# SCH_nfc-card_2024-10-30.net
KiCad netlist of a schematic drawn in EasyEDA
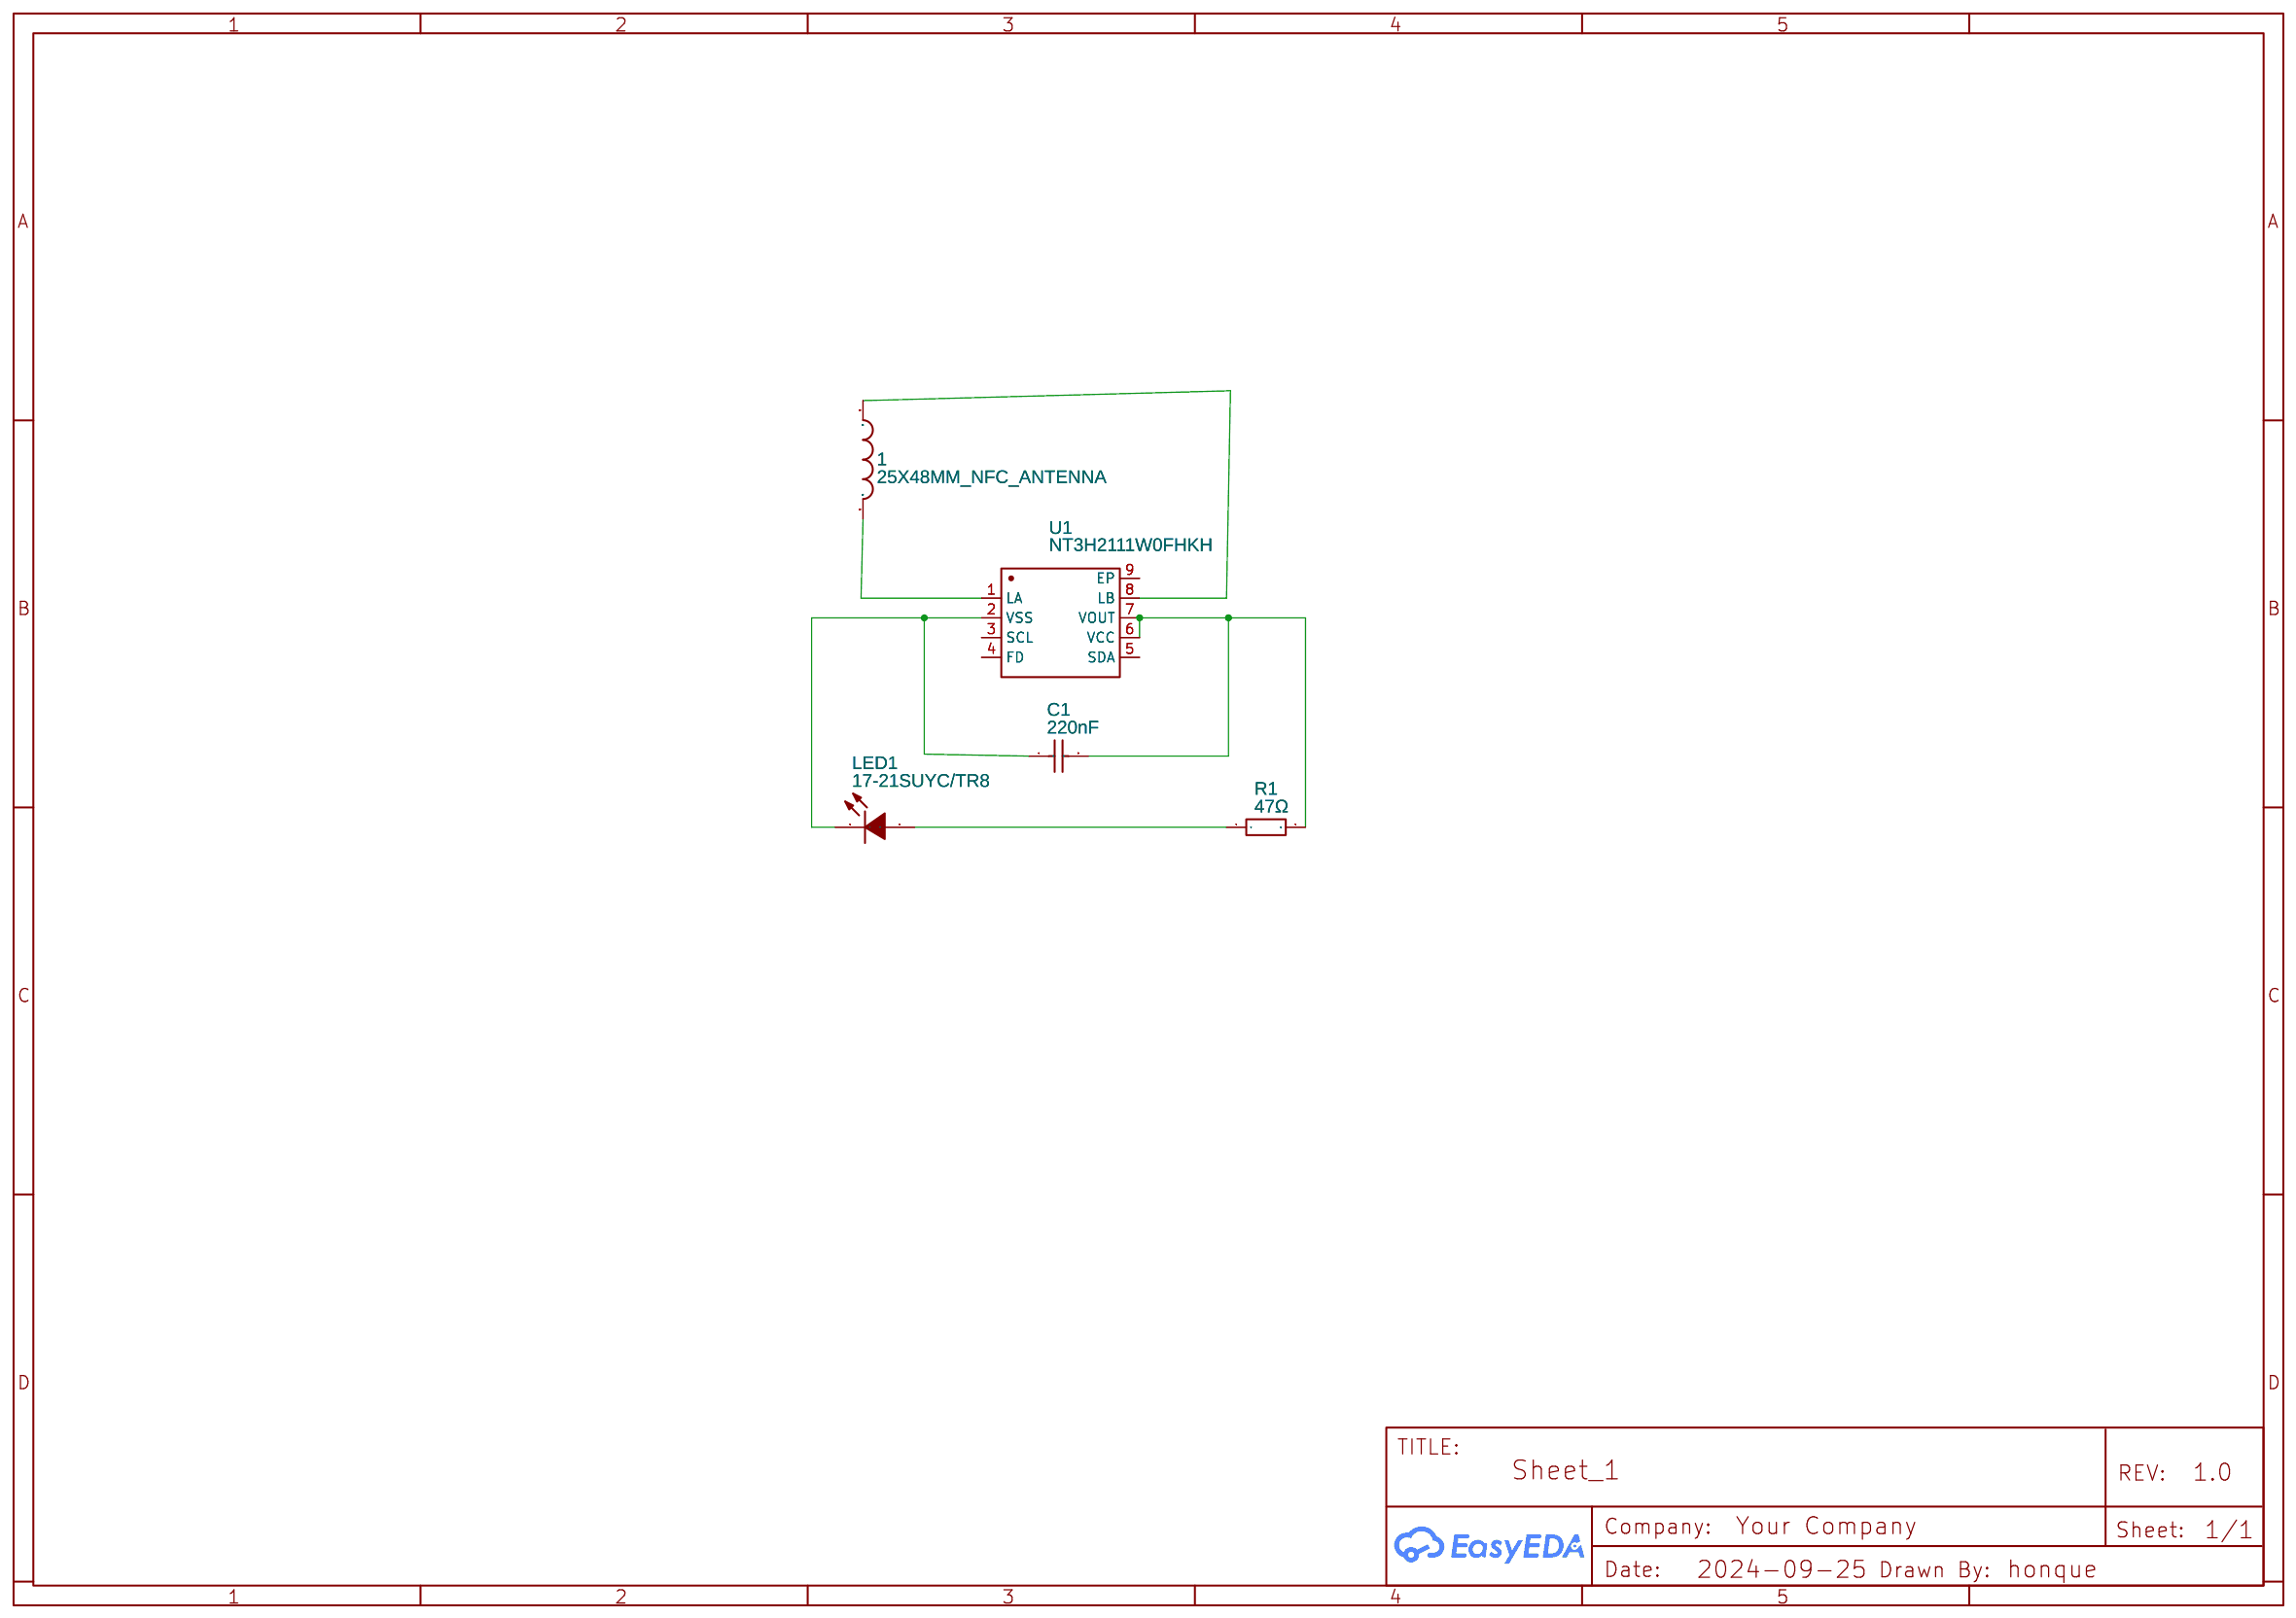
[diagram p0: schematic sheet]

(export (version "E")
  (design (tool "Eeschema 10.0.6"))
  (components
    (comp (ref "1") (value "25X48MM_NFC_ANTENNA") (libsource (lib "") (part "25X48MM_NFC_ANTENNA")))
    (comp (ref "C1")
      (value "220nF")
      (fields
        (field (name "Manufacturer Part") "CL10B224KA8NNNC")
        (field (name "Manufacturer") "SAMSUNG(三星)")
      )
      (libsource (lib "") (part "CL10B224KA8NNNC"))
    )
    (comp (ref "LED1")
      (value "17-21SUYC/TR8")
      (fields (field (name "Manufacturer Part") "KT-0805黄灯") (field (name "Manufacturer") "KENTO"))
      (libsource (lib "") (part "17-21SUYC/TR8"))
    )
    (comp (ref "R1")
      (value "47Ω")
      (fields
        (field (name "Manufacturer Part") "0603WAF470JT5E")
        (field (name "Manufacturer") "UNI-ROYAL(厚声)")
      )
      (libsource (lib "") (part "0603WAF470JT5E"))
    )
    (comp (ref "U1")
      (value "NT3H2111W0FHKH")
      (fields (field (name "Manufacturer") "NXP(恩智浦)"))
      (libsource (lib "") (part "NT3H2111W0FHKH"))
    )
  )
  (nets
    (net (code "1") (name "Net-(LED1-+)") (class "Default")
      (node (ref "LED1") (pin "1") (pinfunction "+_1") (pintype "unspecified"))
      (node (ref "R1") (pin "1") (pinfunction "1_1") (pintype "input"))
    )
    (net (code "2") (name "Net-(LED1--)") (class "Default")
      (node (ref "C1") (pin "1") (pinfunction "1_1") (pintype "input"))
      (node (ref "LED1") (pin "2") (pinfunction "-_2") (pintype "unspecified"))
      (node (ref "U1") (pin "2") (pinfunction "VSS_2") (pintype "unspecified"))
    )
    (net (code "3") (name "Net-(U1-LA)") (class "Default")
      (node (ref "1") (pin "P$2") (pinfunction "P$2_P$2") (pintype "bidirectional"))
      (node (ref "U1") (pin "1") (pinfunction "LA_1") (pintype "unspecified"))
    )
    (net (code "4") (name "Net-(U1-LB)") (class "Default")
      (node (ref "1") (pin "P$1") (pinfunction "P$1_P$1") (pintype "bidirectional"))
      (node (ref "U1") (pin "8") (pinfunction "LB_8") (pintype "unspecified"))
    )
    (net (code "5") (name "Net-(U1-VCC)") (class "Default")
      (node (ref "C1") (pin "2") (pinfunction "2_2") (pintype "input"))
      (node (ref "R1") (pin "2") (pinfunction "2_2") (pintype "input"))
      (node (ref "U1") (pin "6") (pinfunction "VCC_6") (pintype "unspecified"))
      (node (ref "U1") (pin "7") (pinfunction "VOUT_7") (pintype "unspecified"))
    )
    (net (code "6") (name "unconnected-(U1-EP-Pad9)") (class "Default")
      (node (ref "U1") (pin "9") (pinfunction "EP_9") (pintype "unspecified"))
    )
    (net (code "7") (name "unconnected-(U1-FD-Pad4)") (class "Default")
      (node (ref "U1") (pin "4") (pinfunction "FD_4") (pintype "unspecified"))
    )
    (net (code "8") (name "unconnected-(U1-SCL-Pad3)") (class "Default")
      (node (ref "U1") (pin "3") (pinfunction "SCL_3") (pintype "unspecified"))
    )
    (net (code "9") (name "unconnected-(U1-SDA-Pad5)") (class "Default")
      (node (ref "U1") (pin "5") (pinfunction "SDA_5") (pintype "unspecified"))
    )
  )
)
